# AS3364_quad_VCA_0402_DIL-non_inv_v1_0.net
KiCad netlist of a schematic drawn in EAGLE
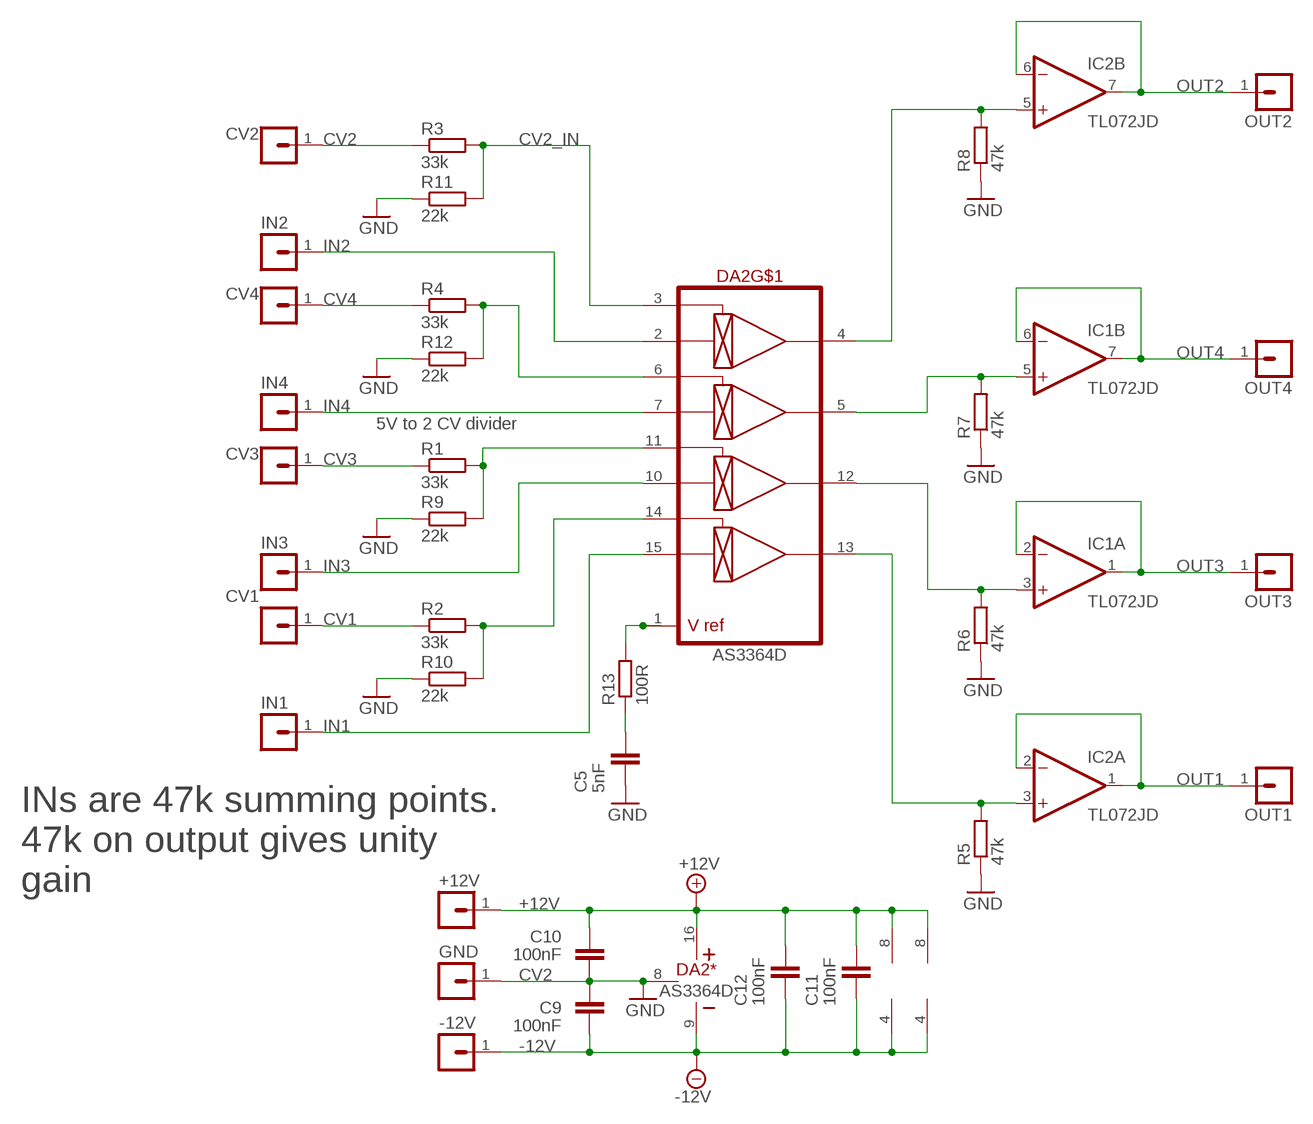
[diagram p0: schematic, sheet 1]

(export (version "E")
  (design (tool "Eeschema 10.0.6"))
  (components
    (comp (ref "+12V")
      (value "MA01-1JP")
      (footprint "eagle-import:SIP-PIN01-1J")
      (libsource (lib "eagle-import") (part "MA01-1JP"))
    )
    (comp (ref "-12V")
      (value "MA01-1JP")
      (footprint "eagle-import:SIP-PIN01-1J")
      (libsource (lib "eagle-import") (part "MA01-1JP"))
    )
    (comp (ref "C5")
      (value "5nF")
      (footprint "eagle-import:C0402")
      (libsource (lib "eagle-import") (part "C-EUC0402"))
    )
    (comp (ref "C9")
      (value "100nF")
      (footprint "eagle-import:C0402")
      (libsource (lib "eagle-import") (part "C-EUC0402"))
    )
    (comp (ref "C10")
      (value "100nF")
      (footprint "eagle-import:C0402")
      (libsource (lib "eagle-import") (part "C-EUC0402"))
    )
    (comp (ref "C11")
      (value "100nF")
      (footprint "eagle-import:C0402")
      (libsource (lib "eagle-import") (part "C-EUC0402"))
    )
    (comp (ref "C12")
      (value "100nF")
      (footprint "eagle-import:C0402")
      (libsource (lib "eagle-import") (part "C-EUC0402"))
    )
    (comp (ref "CV1")
      (value "MA01-1JP")
      (footprint "eagle-import:SIP-PIN01-1J")
      (libsource (lib "eagle-import") (part "MA01-1JP"))
    )
    (comp (ref "CV2")
      (value "MA01-1JP")
      (footprint "eagle-import:SIP-PIN01-1J")
      (libsource (lib "eagle-import") (part "MA01-1JP"))
    )
    (comp (ref "CV3")
      (value "MA01-1JP")
      (footprint "eagle-import:SIP-PIN01-1J")
      (libsource (lib "eagle-import") (part "MA01-1JP"))
    )
    (comp (ref "CV4")
      (value "MA01-1JP")
      (footprint "eagle-import:SIP-PIN01-1J")
      (libsource (lib "eagle-import") (part "MA01-1JP"))
    )
    (comp (ref "DA2")
      (value "AS3364D")
      (footprint "eagle-import:DIL16J")
      (libsource (lib "eagle-import") (part "AS3364D"))
    )
    (comp (ref "GND")
      (value "MA01-1JP")
      (footprint "eagle-import:SIP-PIN01-1J")
      (libsource (lib "eagle-import") (part "MA01-1JP"))
    )
    (comp (ref "IC1")
      (value "TL072JD")
      (footprint "eagle-import:SO08J")
      (libsource (lib "eagle-import") (part "TL072JD"))
    )
    (comp (ref "IC2")
      (value "TL072JD")
      (footprint "eagle-import:SO08J")
      (libsource (lib "eagle-import") (part "TL072JD"))
    )
    (comp (ref "IN1")
      (value "MA01-1JP")
      (footprint "eagle-import:SIP-PIN01-1J")
      (libsource (lib "eagle-import") (part "MA01-1JP"))
    )
    (comp (ref "IN2")
      (value "MA01-1JP")
      (footprint "eagle-import:SIP-PIN01-1J")
      (libsource (lib "eagle-import") (part "MA01-1JP"))
    )
    (comp (ref "IN3")
      (value "MA01-1JP")
      (footprint "eagle-import:SIP-PIN01-1J")
      (libsource (lib "eagle-import") (part "MA01-1JP"))
    )
    (comp (ref "IN4")
      (value "MA01-1JP")
      (footprint "eagle-import:SIP-PIN01-1J")
      (libsource (lib "eagle-import") (part "MA01-1JP"))
    )
    (comp (ref "OUT1")
      (value "MA01-1JP")
      (footprint "eagle-import:SIP-PIN01-1J")
      (libsource (lib "eagle-import") (part "MA01-1JP"))
    )
    (comp (ref "OUT2")
      (value "MA01-1JP")
      (footprint "eagle-import:SIP-PIN01-1J")
      (libsource (lib "eagle-import") (part "MA01-1JP"))
    )
    (comp (ref "OUT3")
      (value "MA01-1JP")
      (footprint "eagle-import:SIP-PIN01-1J")
      (libsource (lib "eagle-import") (part "MA01-1JP"))
    )
    (comp (ref "OUT4")
      (value "MA01-1JP")
      (footprint "eagle-import:SIP-PIN01-1J")
      (libsource (lib "eagle-import") (part "MA01-1JP"))
    )
    (comp (ref "R1")
      (value "33k")
      (footprint "eagle-import:R0402")
      (libsource (lib "eagle-import") (part "R-EU_R0402"))
    )
    (comp (ref "R2")
      (value "33k")
      (footprint "eagle-import:R0402")
      (libsource (lib "eagle-import") (part "R-EU_R0402"))
    )
    (comp (ref "R3")
      (value "33k")
      (footprint "eagle-import:R0402")
      (libsource (lib "eagle-import") (part "R-EU_R0402"))
    )
    (comp (ref "R4")
      (value "33k")
      (footprint "eagle-import:R0402")
      (libsource (lib "eagle-import") (part "R-EU_R0402"))
    )
    (comp (ref "R5")
      (value "47k")
      (footprint "eagle-import:R0402")
      (libsource (lib "eagle-import") (part "R-EU_R0402"))
    )
    (comp (ref "R6")
      (value "47k")
      (footprint "eagle-import:R0402")
      (libsource (lib "eagle-import") (part "R-EU_R0402"))
    )
    (comp (ref "R7")
      (value "47k")
      (footprint "eagle-import:R0402")
      (libsource (lib "eagle-import") (part "R-EU_R0402"))
    )
    (comp (ref "R8")
      (value "47k")
      (footprint "eagle-import:R0402")
      (libsource (lib "eagle-import") (part "R-EU_R0402"))
    )
    (comp (ref "R9")
      (value "22k")
      (footprint "eagle-import:R0402")
      (libsource (lib "eagle-import") (part "R-EU_R0402"))
    )
    (comp (ref "R10")
      (value "22k")
      (footprint "eagle-import:R0402")
      (libsource (lib "eagle-import") (part "R-EU_R0402"))
    )
    (comp (ref "R11")
      (value "22k")
      (footprint "eagle-import:R0402")
      (libsource (lib "eagle-import") (part "R-EU_R0402"))
    )
    (comp (ref "R12")
      (value "22k")
      (footprint "eagle-import:R0402")
      (libsource (lib "eagle-import") (part "R-EU_R0402"))
    )
    (comp (ref "R13")
      (value "100R")
      (footprint "eagle-import:R0402")
      (libsource (lib "eagle-import") (part "R-EU_R0402"))
    )
  )
  (nets
    (net (code "1") (name "+12V") (class "Default")
      (node (ref "+12V") (pin "1") (pinfunction "1_1") (pintype "passive"))
      (node (ref "C10") (pin "2") (pinfunction "2_2") (pintype "passive"))
      (node (ref "C11") (pin "2") (pinfunction "2_2") (pintype "passive"))
      (node (ref "C12") (pin "2") (pinfunction "2_2") (pintype "passive"))
      (node (ref "DA2") (pin "16") (pinfunction "V+_16") (pintype "power_in"))
      (node (ref "IC1") (pin "8") (pinfunction "V+_8") (pintype "power_in"))
      (node (ref "IC2") (pin "8") (pinfunction "V+_8") (pintype "power_in"))
    )
    (net (code "2") (name "-12V") (class "Default")
      (node (ref "-12V") (pin "1") (pinfunction "1_1") (pintype "passive"))
      (node (ref "C11") (pin "1") (pinfunction "1_1") (pintype "passive"))
      (node (ref "C12") (pin "1") (pinfunction "1_1") (pintype "passive"))
      (node (ref "C9") (pin "1") (pinfunction "1_1") (pintype "passive"))
      (node (ref "DA2") (pin "9") (pinfunction "V-_9") (pintype "power_in"))
      (node (ref "IC1") (pin "4") (pinfunction "V-_4") (pintype "power_in"))
      (node (ref "IC2") (pin "4") (pinfunction "V-_4") (pintype "power_in"))
    )
    (net (code "3") (name "/CV1") (class "Default")
      (node (ref "CV1") (pin "1") (pinfunction "1_1") (pintype "passive"))
      (node (ref "R2") (pin "1") (pinfunction "1_1") (pintype "passive"))
    )
    (net (code "4") (name "/CV2") (class "Default")
      (node (ref "CV2") (pin "1") (pinfunction "1_1") (pintype "passive"))
      (node (ref "R3") (pin "1") (pinfunction "1_1") (pintype "passive"))
    )
    (net (code "5") (name "/CV2_IN") (class "Default")
      (node (ref "DA2") (pin "3") (pinfunction "CV1_3") (pintype "input"))
      (node (ref "R11") (pin "2") (pinfunction "2_2") (pintype "passive"))
      (node (ref "R3") (pin "2") (pinfunction "2_2") (pintype "passive"))
    )
    (net (code "6") (name "/CV3") (class "Default")
      (node (ref "CV3") (pin "1") (pinfunction "1_1") (pintype "passive"))
      (node (ref "R1") (pin "1") (pinfunction "1_1") (pintype "passive"))
    )
    (net (code "7") (name "/CV4") (class "Default")
      (node (ref "CV4") (pin "1") (pinfunction "1_1") (pintype "passive"))
      (node (ref "R4") (pin "1") (pinfunction "1_1") (pintype "passive"))
    )
    (net (code "8") (name "/IN1") (class "Default")
      (node (ref "DA2") (pin "15") (pinfunction "IN4_15") (pintype "input"))
      (node (ref "IN1") (pin "1") (pinfunction "1_1") (pintype "passive"))
    )
    (net (code "9") (name "/IN2") (class "Default")
      (node (ref "DA2") (pin "2") (pinfunction "IN1_2") (pintype "input"))
      (node (ref "IN2") (pin "1") (pinfunction "1_1") (pintype "passive"))
    )
    (net (code "10") (name "/IN3") (class "Default")
      (node (ref "DA2") (pin "10") (pinfunction "IN3_10") (pintype "input"))
      (node (ref "IN3") (pin "1") (pinfunction "1_1") (pintype "passive"))
    )
    (net (code "11") (name "/IN4") (class "Default")
      (node (ref "DA2") (pin "7") (pinfunction "IN2_7") (pintype "input"))
      (node (ref "IN4") (pin "1") (pinfunction "1_1") (pintype "passive"))
    )
    (net (code "12") (name "/OUT1") (class "Default")
      (node (ref "IC2") (pin "1") (pinfunction "OUT_1") (pintype "output"))
      (node (ref "IC2") (pin "2") (pinfunction "-IN_2") (pintype "input"))
      (node (ref "OUT1") (pin "1") (pinfunction "1_1") (pintype "passive"))
    )
    (net (code "13") (name "/OUT2") (class "Default")
      (node (ref "IC2") (pin "6") (pinfunction "-IN_6") (pintype "input"))
      (node (ref "IC2") (pin "7") (pinfunction "OUT_7") (pintype "output"))
      (node (ref "OUT2") (pin "1") (pinfunction "1_1") (pintype "passive"))
    )
    (net (code "14") (name "/OUT3") (class "Default")
      (node (ref "IC1") (pin "1") (pinfunction "OUT_1") (pintype "output"))
      (node (ref "IC1") (pin "2") (pinfunction "-IN_2") (pintype "input"))
      (node (ref "OUT3") (pin "1") (pinfunction "1_1") (pintype "passive"))
    )
    (net (code "15") (name "/OUT4") (class "Default")
      (node (ref "IC1") (pin "6") (pinfunction "-IN_6") (pintype "input"))
      (node (ref "IC1") (pin "7") (pinfunction "OUT_7") (pintype "output"))
      (node (ref "OUT4") (pin "1") (pinfunction "1_1") (pintype "passive"))
    )
    (net (code "16") (name "GND") (class "Default")
      (node (ref "C10") (pin "1") (pinfunction "1_1") (pintype "passive"))
      (node (ref "C5") (pin "1") (pinfunction "1_1") (pintype "passive"))
      (node (ref "C9") (pin "2") (pinfunction "2_2") (pintype "passive"))
      (node (ref "DA2") (pin "8") (pinfunction "GND_8") (pintype "power_in"))
      (node (ref "GND") (pin "1") (pinfunction "1_1") (pintype "passive"))
      (node (ref "R10") (pin "1") (pinfunction "1_1") (pintype "passive"))
      (node (ref "R11") (pin "1") (pinfunction "1_1") (pintype "passive"))
      (node (ref "R12") (pin "1") (pinfunction "1_1") (pintype "passive"))
      (node (ref "R5") (pin "1") (pinfunction "1_1") (pintype "passive"))
      (node (ref "R6") (pin "1") (pinfunction "1_1") (pintype "passive"))
      (node (ref "R7") (pin "1") (pinfunction "1_1") (pintype "passive"))
      (node (ref "R8") (pin "1") (pinfunction "1_1") (pintype "passive"))
      (node (ref "R9") (pin "1") (pinfunction "1_1") (pintype "passive"))
    )
    (net (code "17") (name "Net-(C5-Pad2)") (class "Default")
      (node (ref "C5") (pin "2") (pinfunction "2_2") (pintype "passive"))
      (node (ref "R13") (pin "1") (pinfunction "1_1") (pintype "passive"))
    )
    (net (code "18") (name "Net-(DA2B-CV2)") (class "Default")
      (node (ref "DA2") (pin "6") (pinfunction "CV2_6") (pintype "input"))
      (node (ref "R12") (pin "2") (pinfunction "2_2") (pintype "passive"))
      (node (ref "R4") (pin "2") (pinfunction "2_2") (pintype "passive"))
    )
    (net (code "19") (name "Net-(DA2B-CV3)") (class "Default")
      (node (ref "DA2") (pin "11") (pinfunction "CV3_11") (pintype "input"))
      (node (ref "R1") (pin "2") (pinfunction "2_2") (pintype "passive"))
      (node (ref "R9") (pin "2") (pinfunction "2_2") (pintype "passive"))
    )
    (net (code "20") (name "Net-(DA2B-CV4)") (class "Default")
      (node (ref "DA2") (pin "14") (pinfunction "CV4_14") (pintype "input"))
      (node (ref "R10") (pin "2") (pinfunction "2_2") (pintype "passive"))
      (node (ref "R2") (pin "2") (pinfunction "2_2") (pintype "passive"))
    )
    (net (code "21") (name "Net-(DA2B-OUT1)") (class "Default")
      (node (ref "DA2") (pin "4") (pinfunction "OUT1_4") (pintype "output"))
      (node (ref "IC2") (pin "5") (pinfunction "+IN_5") (pintype "input"))
      (node (ref "R8") (pin "2") (pinfunction "2_2") (pintype "passive"))
    )
    (net (code "22") (name "Net-(DA2B-OUT2)") (class "Default")
      (node (ref "DA2") (pin "5") (pinfunction "OUT2_5") (pintype "output"))
      (node (ref "IC1") (pin "5") (pinfunction "+IN_5") (pintype "input"))
      (node (ref "R7") (pin "2") (pinfunction "2_2") (pintype "passive"))
    )
    (net (code "23") (name "Net-(DA2B-OUT3)") (class "Default")
      (node (ref "DA2") (pin "12") (pinfunction "OUT3_12") (pintype "output"))
      (node (ref "IC1") (pin "3") (pinfunction "+IN_3") (pintype "input"))
      (node (ref "R6") (pin "2") (pinfunction "2_2") (pintype "passive"))
    )
    (net (code "24") (name "Net-(DA2B-OUT4)") (class "Default")
      (node (ref "DA2") (pin "13") (pinfunction "OUT4_13") (pintype "output"))
      (node (ref "IC2") (pin "3") (pinfunction "+IN_3") (pintype "input"))
      (node (ref "R5") (pin "2") (pinfunction "2_2") (pintype "passive"))
    )
    (net (code "25") (name "Net-(DA2B-VREF)") (class "Default")
      (node (ref "DA2") (pin "1") (pinfunction "VREF_1") (pintype "output"))
      (node (ref "R13") (pin "2") (pinfunction "2_2") (pintype "passive"))
    )
  )
)
